# untitled-1_1.net
KiCad netlist of a schematic drawn in EAGLE
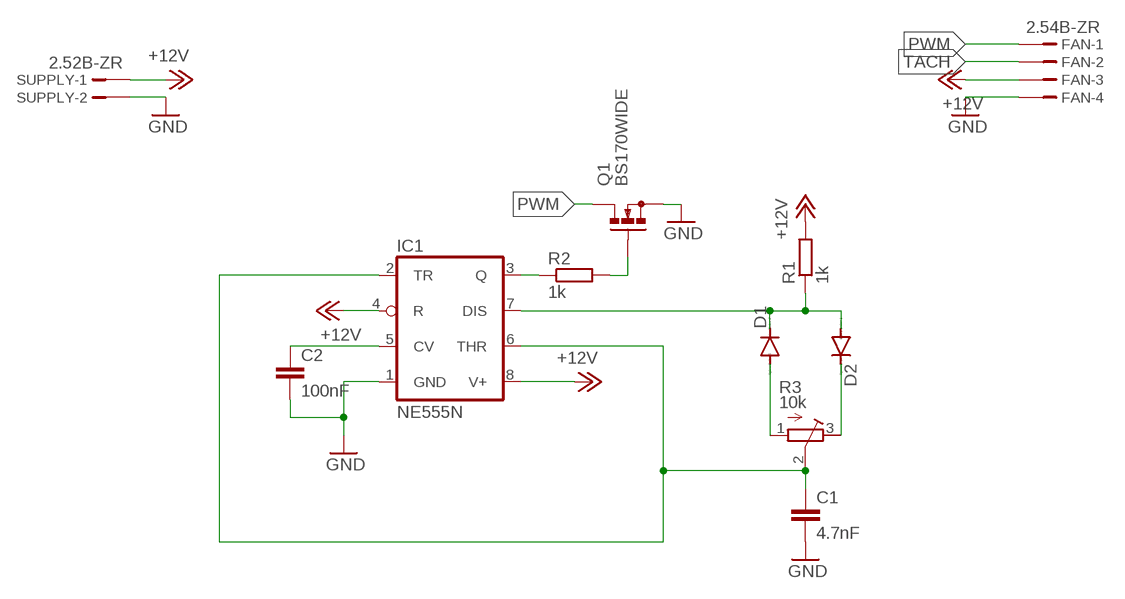
[diagram p0: schematic, sheet 1]

(export (version "E")
  (design (tool "Eeschema 10.0.6"))
  (components
    (comp (ref "C1")
      (value "4.7nF")
      (footprint "eagle-import:C050-030X075")
      (libsource (lib "eagle-import") (part "C-EU050-030X075"))
    )
    (comp (ref "C2")
      (value "100nF")
      (footprint "eagle-import:C025-025X050")
      (libsource (lib "eagle-import") (part "C-EU025-025X050"))
    )
    (comp (ref "D1")
      (value "1N40045")
      (footprint "eagle-import:DO41-5")
      (libsource (lib "eagle-import") (part "1N40045"))
    )
    (comp (ref "D2")
      (value "1N40045")
      (footprint "eagle-import:DO41-5")
      (libsource (lib "eagle-import") (part "1N40045"))
    )
    (comp (ref "FAN")
      (value "2.54B-ZR")
      (footprint "eagle-import:B4B-ZR2.5")
      (libsource (lib "eagle-import") (part "?4B-ZR2.5"))
    )
    (comp (ref "IC1")
      (value "NE555N")
      (footprint "eagle-import:DIL08")
      (libsource (lib "eagle-import") (part "555NNE"))
    )
    (comp (ref "Q1")
      (value "BS170WIDE")
      (footprint "eagle-import:SOT54E2")
      (libsource (lib "eagle-import") (part "BS170WIDE"))
    )
    (comp (ref "R1")
      (value "1k")
      (footprint "eagle-import:0204_7")
      (libsource (lib "eagle-import") (part "R-EU_0204/7"))
    )
    (comp (ref "R2")
      (value "1k")
      (footprint "eagle-import:0204_7")
      (libsource (lib "eagle-import") (part "R-EU_0204/7"))
    )
    (comp (ref "R3")
      (value "10k")
      (footprint "eagle-import:RTRIM3296W")
      (libsource (lib "eagle-import") (part "R-TRIMM3296W"))
    )
    (comp (ref "SUPPLY")
      (value "2.52B-ZR")
      (footprint "eagle-import:B2B-ZR2.5")
      (libsource (lib "eagle-import") (part "?2B-ZR2.5"))
    )
  )
  (nets
    (net (code "1") (name "+12V") (class "Default")
      (node (ref "FAN") (pin "3") (pinfunction "1_3") (pintype "passive"))
      (node (ref "IC1") (pin "4") (pinfunction "R_4") (pintype "input"))
      (node (ref "IC1") (pin "8") (pinfunction "V+_8") (pintype "power_in"))
      (node (ref "R1") (pin "2") (pinfunction "2_2") (pintype "passive"))
      (node (ref "SUPPLY") (pin "1") (pinfunction "1_1") (pintype "passive"))
    )
    (net (code "2") (name "GND") (class "Default")
      (node (ref "C1") (pin "2") (pinfunction "2_2") (pintype "passive"))
      (node (ref "C2") (pin "2") (pinfunction "2_2") (pintype "passive"))
      (node (ref "FAN") (pin "4") (pinfunction "1_4") (pintype "passive"))
      (node (ref "IC1") (pin "1") (pinfunction "GND_1") (pintype "power_in"))
      (node (ref "Q1") (pin "S") (pinfunction "S_S") (pintype "passive"))
      (node (ref "SUPPLY") (pin "2") (pinfunction "1_2") (pintype "passive"))
    )
    (net (code "3") (name "Net-(IC1-CV)") (class "Default")
      (node (ref "C2") (pin "1") (pinfunction "1_1") (pintype "passive"))
      (node (ref "IC1") (pin "5") (pinfunction "CV_5") (pintype "input"))
    )
    (net (code "4") (name "Net-(IC1-DIS)") (class "Default")
      (node (ref "D1") (pin "C") (pinfunction "C_C") (pintype "passive"))
      (node (ref "D2") (pin "A") (pinfunction "A_A") (pintype "passive"))
      (node (ref "IC1") (pin "7") (pinfunction "DIS_7") (pintype "input"))
      (node (ref "R1") (pin "1") (pinfunction "1_1") (pintype "passive"))
    )
    (net (code "5") (name "Net-(IC1-Q)") (class "Default")
      (node (ref "IC1") (pin "3") (pinfunction "Q_3") (pintype "output"))
      (node (ref "R2") (pin "1") (pinfunction "1_1") (pintype "passive"))
    )
    (net (code "6") (name "Net-(IC1-THR)") (class "Default")
      (node (ref "C1") (pin "1") (pinfunction "1_1") (pintype "passive"))
      (node (ref "IC1") (pin "2") (pinfunction "TR_2") (pintype "input"))
      (node (ref "IC1") (pin "6") (pinfunction "THR_6") (pintype "input"))
      (node (ref "R3") (pin "2") (pinfunction "S_2") (pintype "passive"))
    )
    (net (code "7") (name "Net-(Q1-PadG)") (class "Default")
      (node (ref "Q1") (pin "G") (pinfunction "G_G") (pintype "passive"))
      (node (ref "R2") (pin "2") (pinfunction "2_2") (pintype "passive"))
    )
    (net (code "8") (name "Net-(R3-A)") (class "Default")
      (node (ref "D1") (pin "A") (pinfunction "A_A") (pintype "passive"))
      (node (ref "R3") (pin "1") (pinfunction "A_1") (pintype "passive"))
    )
    (net (code "9") (name "Net-(R3-E)") (class "Default")
      (node (ref "D2") (pin "C") (pinfunction "C_C") (pintype "passive"))
      (node (ref "R3") (pin "3") (pinfunction "E_3") (pintype "passive"))
    )
    (net (code "10") (name "PWM") (class "Default")
      (node (ref "FAN") (pin "1") (pinfunction "1_1") (pintype "passive"))
      (node (ref "Q1") (pin "D") (pinfunction "D_D") (pintype "passive"))
    )
    (net (code "11") (name "TACH") (class "Default")
      (node (ref "FAN") (pin "2") (pinfunction "1_2") (pintype "passive"))
    )
  )
)
